# tricorder-teensy-mk-1_12_1.net
KiCad netlist of a schematic drawn in EAGLE
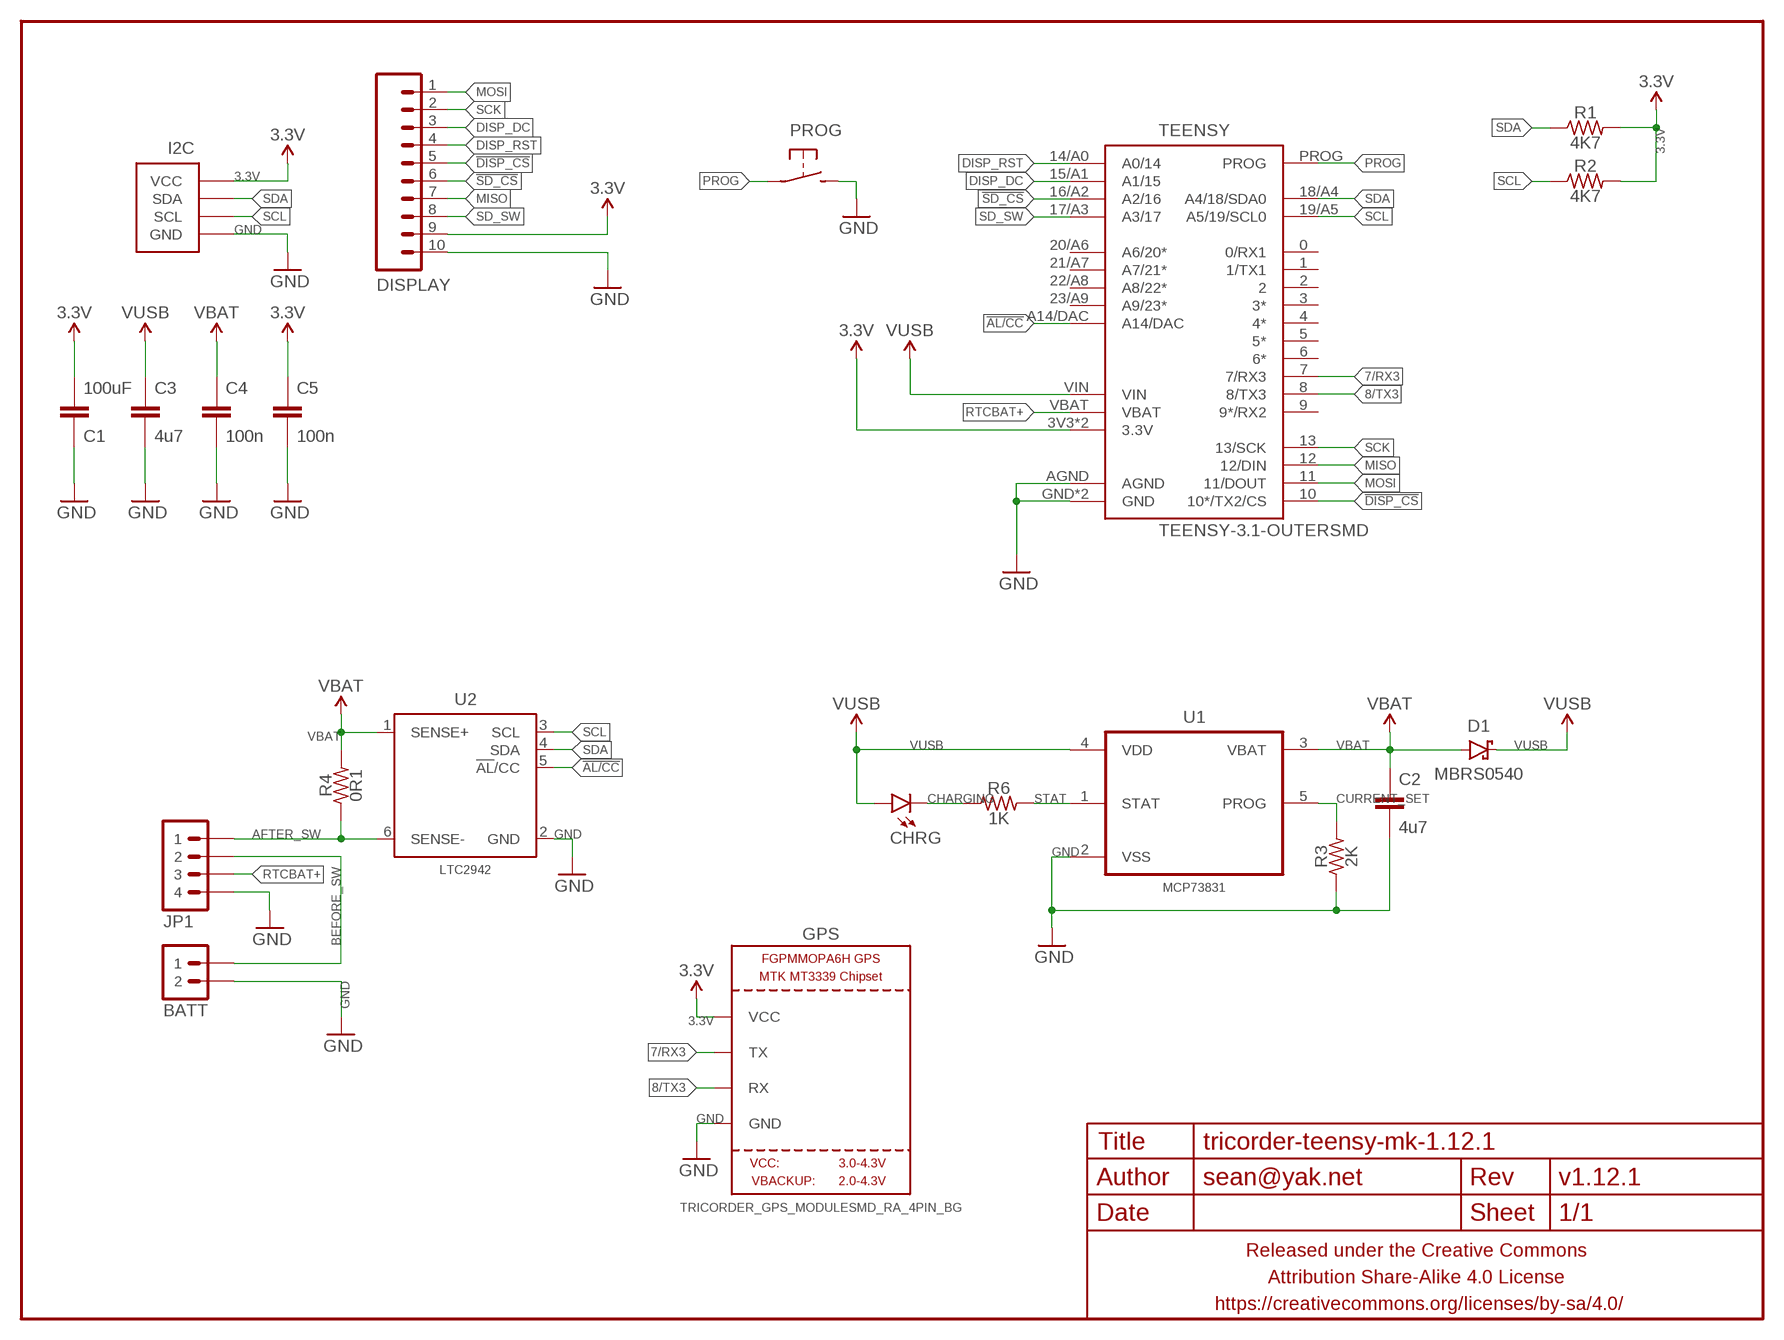
[diagram p0: schematic, sheet 1]

(export (version "E")
  (design (tool "Eeschema 10.0.6"))
  (components
    (comp (ref "BATT")
      (value "M02JST-2MM-SMT")
      (footprint "eagle-import:JST-2-SMD")
      (libsource (lib "eagle-import") (part "M02JST-2MM-SMT"))
    )
    (comp (ref "C1")
      (value "100uF")
      (footprint "eagle-import:C1210")
      (libsource (lib "eagle-import") (part "CAPACITOR-CERAMICC1210"))
    )
    (comp (ref "C2")
      (value "4u7")
      (footprint "eagle-import:C0603-TIGHTER")
      (libsource (lib "eagle-import") (part "CAPACITOR-CERAMICC0603-TIGHTER"))
    )
    (comp (ref "C3")
      (value "4u7")
      (footprint "eagle-import:C0603-TIGHTER")
      (libsource (lib "eagle-import") (part "CAPACITOR-CERAMICC0603-TIGHTER"))
    )
    (comp (ref "C4")
      (value "100n")
      (footprint "eagle-import:C0603-TIGHTER")
      (libsource (lib "eagle-import") (part "CAPACITOR-CERAMICC0603-TIGHTER"))
    )
    (comp (ref "C5")
      (value "100n")
      (footprint "eagle-import:C0603-TIGHTER")
      (libsource (lib "eagle-import") (part "CAPACITOR-CERAMICC0603-TIGHTER"))
    )
    (comp (ref "CHRG")
      (value "LED0603-TIGHT")
      (footprint "eagle-import:LED-0603-TIGHT")
      (libsource (lib "eagle-import") (part "LED0603-TIGHT"))
    )
    (comp (ref "D1")
      (value "MBRS0540")
      (footprint "eagle-import:SOD123-SCHOTTKY")
      (libsource (lib "eagle-import") (part "DIODE-SCHOTTKYSOD123"))
    )
    (comp (ref "DISPLAY")
      (value "M10SMD_RA_2MM")
      (footprint "eagle-import:1X10_SMD_RA_MALE")
      (libsource (lib "eagle-import") (part "M10SMD_RA_2MM"))
    )
    (comp (ref "FRAME1")
      (value "FRAME-LETTERNO_PACKAGE")
      (footprint "eagle-import:DUMMY")
      (fields
        (field (name "DESIGNER") "Nobody")
        (field (name "VERSION") "v01")
        (field (name "DESIGNER_1") "sean@yak.net")
        (field (name "VERSION_1") "v1.12.1")
      )
      (libsource (lib "eagle-import") (part "FRAME-LETTERNO_PACKAGE"))
    )
    (comp (ref "GPS")
      (value "TRICORDER_GPS_MODULESMD_RA_4PIN_BG")
      (footprint "eagle-import:TRICORDER_GPS_MODULE_RA_CONN_SMD_4PIN_BG")
      (libsource (lib "eagle-import") (part "TRICORDER_GPS_MODULESMD_RA_4PIN_BG"))
    )
    (comp (ref "I2C")
      (value "M04-I2CSMD_2MM_RA")
      (footprint "eagle-import:1X04_SMD_RA_2MM_I2C")
      (libsource (lib "eagle-import") (part "M04-I2CSMD_2MM_RA"))
    )
    (comp (ref "JP1")
      (value "M04SMD_RA_2MM")
      (footprint "eagle-import:1X04_SMD_RA_2MM")
      (libsource (lib "eagle-import") (part "M04SMD_RA_2MM"))
    )
    (comp (ref "PROG")
      (value "SPST-NO-TACTCK-PTS840-GK")
      (footprint "eagle-import:TACTILE-SMD-CK-PTS840-GK")
      (libsource (lib "eagle-import") (part "SPST-NO-TACTCK-PTS840-GK"))
    )
    (comp (ref "R1")
      (value "4K7")
      (footprint "eagle-import:R0603-TIGHTER")
      (libsource (lib "eagle-import") (part "RESISTORR0603-TIGHTER"))
    )
    (comp (ref "R2")
      (value "4K7")
      (footprint "eagle-import:R0603-TIGHTER")
      (libsource (lib "eagle-import") (part "RESISTORR0603-TIGHTER"))
    )
    (comp (ref "R3")
      (value "2K")
      (footprint "eagle-import:R0603-TIGHTER")
      (libsource (lib "eagle-import") (part "RESISTORR0603-TIGHTER"))
    )
    (comp (ref "R4")
      (value "0R1")
      (footprint "eagle-import:R0805-TIGHTER")
      (libsource (lib "eagle-import") (part "RESISTORR0805-TIGHTER"))
    )
    (comp (ref "R6")
      (value "1K")
      (footprint "eagle-import:R0603-TIGHTER")
      (libsource (lib "eagle-import") (part "RESISTORR0603-TIGHTER"))
    )
    (comp (ref "TEENSY")
      (value "TEENSY-3.1-OUTERSMD")
      (footprint "eagle-import:TEENSY-3.1_SMT_BOTTOM_OUTERONLY")
      (libsource (lib "eagle-import") (part "TEENSY-3.1-OUTERSMD"))
    )
    (comp (ref "U1")
      (value "MCP73831")
      (footprint "eagle-import:SOT95P280X145-5N")
      (fields (field (name "MPN") "MCP73831T-2ACI/OT"))
      (libsource (lib "eagle-import") (part "MCP73831T-2ACI/OT"))
    )
    (comp (ref "U2")
      (value "LTC2942")
      (footprint "eagle-import:DFN200X300X50-7N")
      (libsource (lib "eagle-import") (part "LTC2941/2DCB"))
    )
  )
  (nets
    (net (code "1") (name "/AFTER_SW") (class "Default")
      (node (ref "JP1") (pin "1") (pinfunction "1_1") (pintype "passive"))
      (node (ref "R4") (pin "1") (pinfunction "1_1") (pintype "passive"))
      (node (ref "U2") (pin "6") (pinfunction "SENSE-_6") (pintype "bidirectional"))
    )
    (net (code "2") (name "/BEFORE_SW") (class "Default")
      (node (ref "BATT") (pin "2") (pinfunction "1_2") (pintype "passive"))
      (node (ref "JP1") (pin "2") (pinfunction "2_2") (pintype "passive"))
    )
    (net (code "3") (name "/CHARGING") (class "Default")
      (node (ref "CHRG") (pin "C") (pinfunction "C_C") (pintype "passive"))
      (node (ref "R6") (pin "1") (pinfunction "1_1") (pintype "passive"))
    )
    (net (code "4") (name "/CURRENT_SET") (class "Default")
      (node (ref "R3") (pin "2") (pinfunction "2_2") (pintype "passive"))
      (node (ref "U1") (pin "5") (pinfunction "PROG_5") (pintype "input"))
    )
    (net (code "5") (name "/STAT") (class "Default")
      (node (ref "R6") (pin "2") (pinfunction "2_2") (pintype "passive"))
      (node (ref "U1") (pin "1") (pinfunction "STAT_1") (pintype "output"))
    )
    (net (code "6") (name "/~{AL{slash}CC}") (class "Default")
      (node (ref "TEENSY") (pin "A14/DAC") (pinfunction "A14/DAC_A14/DAC") (pintype "bidirectional"))
      (node (ref "U2") (pin "5") (pinfunction "~{AL}/CC_5") (pintype "bidirectional"))
    )
    (net (code "7") (name "/~{DISP_CS}") (class "Default")
      (node (ref "DISPLAY") (pin "5") (pinfunction "5_5") (pintype "passive"))
      (node (ref "TEENSY") (pin "10") (pinfunction "10*/TX2/CS_10") (pintype "bidirectional"))
    )
    (net (code "8") (name "/~{SD_CS}") (class "Default")
      (node (ref "DISPLAY") (pin "6") (pinfunction "6_6") (pintype "passive"))
      (node (ref "TEENSY") (pin "16/A2") (pinfunction "A2/16_16/A2") (pintype "bidirectional"))
    )
    (net (code "9") (name "3.3V") (class "Default")
      (node (ref "C1") (pin "2") (pinfunction "2_2") (pintype "passive"))
      (node (ref "C5") (pin "1") (pinfunction "1_1") (pintype "passive"))
      (node (ref "DISPLAY") (pin "9") (pinfunction "9_9") (pintype "passive"))
      (node (ref "GPS") (pin "VCC") (pinfunction "VCC_VCC") (pintype "bidirectional"))
      (node (ref "I2C") (pin "VCC") (pinfunction "VCC_VCC") (pintype "bidirectional"))
      (node (ref "R1") (pin "2") (pinfunction "2_2") (pintype "passive"))
      (node (ref "R2") (pin "2") (pinfunction "2_2") (pintype "passive"))
      (node (ref "TEENSY") (pin "3V3") (pinfunction "3.3V_3V3") (pintype "bidirectional"))
      (node (ref "TEENSY") (pin "3V3@1") (pinfunction "3.3V_3V3@1") (pintype "bidirectional"))
    )
    (net (code "10") (name "7{slash}RX3") (class "Default")
      (node (ref "GPS") (pin "TX") (pinfunction "TX_TX") (pintype "bidirectional"))
      (node (ref "TEENSY") (pin "7") (pinfunction "7/RX3_7") (pintype "bidirectional"))
    )
    (net (code "11") (name "8{slash}TX3") (class "Default")
      (node (ref "GPS") (pin "RX") (pinfunction "RX_RX") (pintype "bidirectional"))
      (node (ref "TEENSY") (pin "8") (pinfunction "8/TX3_8") (pintype "bidirectional"))
    )
    (net (code "12") (name "DISP_DC") (class "Default")
      (node (ref "DISPLAY") (pin "3") (pinfunction "3_3") (pintype "passive"))
      (node (ref "TEENSY") (pin "15/A1") (pinfunction "A1/15_15/A1") (pintype "bidirectional"))
    )
    (net (code "13") (name "DISP_RST") (class "Default")
      (node (ref "DISPLAY") (pin "4") (pinfunction "4_4") (pintype "passive"))
      (node (ref "TEENSY") (pin "14/A0") (pinfunction "A0/14_14/A0") (pintype "bidirectional"))
    )
    (net (code "14") (name "GND") (class "Default")
      (node (ref "BATT") (pin "1") (pinfunction "2_1") (pintype "passive"))
      (node (ref "C1") (pin "1") (pinfunction "1_1") (pintype "passive"))
      (node (ref "C2") (pin "2") (pinfunction "2_2") (pintype "passive"))
      (node (ref "C3") (pin "2") (pinfunction "2_2") (pintype "passive"))
      (node (ref "C4") (pin "2") (pinfunction "2_2") (pintype "passive"))
      (node (ref "C5") (pin "2") (pinfunction "2_2") (pintype "passive"))
      (node (ref "DISPLAY") (pin "10") (pinfunction "10_10") (pintype "passive"))
      (node (ref "GPS") (pin "GND") (pinfunction "GND_GND") (pintype "bidirectional"))
      (node (ref "I2C") (pin "GND") (pinfunction "GND_GND") (pintype "bidirectional"))
      (node (ref "JP1") (pin "4") (pinfunction "4_4") (pintype "passive"))
      (node (ref "PROG") (pin "3") (pinfunction "2_3") (pintype "passive"))
      (node (ref "PROG") (pin "4") (pinfunction "2_4") (pintype "passive"))
      (node (ref "R3") (pin "1") (pinfunction "1_1") (pintype "passive"))
      (node (ref "TEENSY") (pin "AGND") (pinfunction "AGND_AGND") (pintype "bidirectional"))
      (node (ref "TEENSY") (pin "GND") (pinfunction "GND_GND") (pintype "bidirectional"))
      (node (ref "TEENSY") (pin "GND@1") (pinfunction "GND_GND@1") (pintype "bidirectional"))
      (node (ref "U1") (pin "2") (pinfunction "VSS_2") (pintype "power_in"))
      (node (ref "U2") (pin "2") (pinfunction "GND_2") (pintype "bidirectional"))
    )
    (net (code "15") (name "MISO") (class "Default")
      (node (ref "DISPLAY") (pin "7") (pinfunction "7_7") (pintype "passive"))
      (node (ref "TEENSY") (pin "12") (pinfunction "12/DIN_12") (pintype "bidirectional"))
    )
    (net (code "16") (name "MOSI") (class "Default")
      (node (ref "DISPLAY") (pin "1") (pinfunction "1_1") (pintype "passive"))
      (node (ref "TEENSY") (pin "11") (pinfunction "11/DOUT_11") (pintype "bidirectional"))
    )
    (net (code "17") (name "PROG") (class "Default")
      (node (ref "PROG") (pin "1") (pinfunction "1_1") (pintype "passive"))
      (node (ref "PROG") (pin "2") (pinfunction "1_2") (pintype "passive"))
      (node (ref "TEENSY") (pin "PROG") (pinfunction "PROG_PROG") (pintype "bidirectional"))
    )
    (net (code "18") (name "RTCBAT+") (class "Default")
      (node (ref "JP1") (pin "3") (pinfunction "3_3") (pintype "passive"))
      (node (ref "TEENSY") (pin "VBAT") (pinfunction "VBAT_VBAT") (pintype "bidirectional"))
    )
    (net (code "19") (name "SCK") (class "Default")
      (node (ref "DISPLAY") (pin "2") (pinfunction "2_2") (pintype "passive"))
      (node (ref "TEENSY") (pin "13") (pinfunction "13/SCK_13") (pintype "bidirectional"))
    )
    (net (code "20") (name "SCL") (class "Default")
      (node (ref "I2C") (pin "SCL") (pinfunction "SCL_SCL") (pintype "bidirectional"))
      (node (ref "R2") (pin "1") (pinfunction "1_1") (pintype "passive"))
      (node (ref "TEENSY") (pin "19/A5") (pinfunction "A5/19/SCL0_19/A5") (pintype "bidirectional"))
      (node (ref "U2") (pin "3") (pinfunction "SCL_3") (pintype "bidirectional"))
    )
    (net (code "21") (name "SDA") (class "Default")
      (node (ref "I2C") (pin "SDA") (pinfunction "SDA_SDA") (pintype "bidirectional"))
      (node (ref "R1") (pin "1") (pinfunction "1_1") (pintype "passive"))
      (node (ref "TEENSY") (pin "18/A4") (pinfunction "A4/18/SDA0_18/A4") (pintype "bidirectional"))
      (node (ref "U2") (pin "4") (pinfunction "SDA_4") (pintype "bidirectional"))
    )
    (net (code "22") (name "SD_SW") (class "Default")
      (node (ref "DISPLAY") (pin "8") (pinfunction "8_8") (pintype "passive"))
      (node (ref "TEENSY") (pin "17/A3") (pinfunction "A3/17_17/A3") (pintype "bidirectional"))
    )
    (net (code "23") (name "VBAT") (class "Default")
      (node (ref "C2") (pin "1") (pinfunction "1_1") (pintype "passive"))
      (node (ref "C4") (pin "1") (pinfunction "1_1") (pintype "passive"))
      (node (ref "D1") (pin "A") (pinfunction "A_A") (pintype "passive"))
      (node (ref "R4") (pin "2") (pinfunction "2_2") (pintype "passive"))
      (node (ref "U1") (pin "3") (pinfunction "VBAT_3") (pintype "output"))
      (node (ref "U2") (pin "1") (pinfunction "SENSE+_1") (pintype "bidirectional"))
    )
    (net (code "24") (name "VUSB") (class "Default")
      (node (ref "C3") (pin "1") (pinfunction "1_1") (pintype "passive"))
      (node (ref "CHRG") (pin "A") (pinfunction "A_A") (pintype "passive"))
      (node (ref "D1") (pin "C") (pinfunction "C_C") (pintype "passive"))
      (node (ref "TEENSY") (pin "VIN") (pinfunction "VIN_VIN") (pintype "bidirectional"))
      (node (ref "U1") (pin "4") (pinfunction "VDD_4") (pintype "power_in"))
    )
    (net (code "25") (name "unconnected-(TEENSY-0{slash}RX1-Pad0)") (class "Default")
      (node (ref "TEENSY") (pin "0") (pinfunction "0/RX1_0") (pintype "bidirectional"))
    )
    (net (code "26") (name "unconnected-(TEENSY-1{slash}TX1-Pad1)") (class "Default")
      (node (ref "TEENSY") (pin "1") (pinfunction "1/TX1_1") (pintype "bidirectional"))
    )
    (net (code "27") (name "unconnected-(TEENSY-3*-Pad3)") (class "Default")
      (node (ref "TEENSY") (pin "3") (pinfunction "3*_3") (pintype "bidirectional"))
    )
    (net (code "28") (name "unconnected-(TEENSY-4*-Pad4)") (class "Default")
      (node (ref "TEENSY") (pin "4") (pinfunction "4*_4") (pintype "bidirectional"))
    )
    (net (code "29") (name "unconnected-(TEENSY-5*-Pad5)") (class "Default")
      (node (ref "TEENSY") (pin "5") (pinfunction "5*_5") (pintype "bidirectional"))
    )
    (net (code "30") (name "unconnected-(TEENSY-6*-Pad6)") (class "Default")
      (node (ref "TEENSY") (pin "6") (pinfunction "6*_6") (pintype "bidirectional"))
    )
    (net (code "31") (name "unconnected-(TEENSY-9*{slash}RX2-Pad9)") (class "Default")
      (node (ref "TEENSY") (pin "9") (pinfunction "9*/RX2_9") (pintype "bidirectional"))
    )
    (net (code "32") (name "unconnected-(TEENSY-A6{slash}20*-Pad20{slash}A6)") (class "Default")
      (node (ref "TEENSY") (pin "20/A6") (pinfunction "A6/20*_20/A6") (pintype "bidirectional"))
    )
    (net (code "33") (name "unconnected-(TEENSY-A7{slash}21*-Pad21{slash}A7)") (class "Default")
      (node (ref "TEENSY") (pin "21/A7") (pinfunction "A7/21*_21/A7") (pintype "bidirectional"))
    )
    (net (code "34") (name "unconnected-(TEENSY-A8{slash}22*-Pad22{slash}A8)") (class "Default")
      (node (ref "TEENSY") (pin "22/A8") (pinfunction "A8/22*_22/A8") (pintype "bidirectional"))
    )
    (net (code "35") (name "unconnected-(TEENSY-A9{slash}23*-Pad23{slash}A9)") (class "Default")
      (node (ref "TEENSY") (pin "23/A9") (pinfunction "A9/23*_23/A9") (pintype "bidirectional"))
    )
    (net (code "36") (name "unconnected-(TEENSY-Pad2)") (class "Default")
      (node (ref "TEENSY") (pin "2") (pinfunction "2_2") (pintype "bidirectional"))
    )
  )
)
